# Connectors_OLD.net
KiCad netlist of a schematic drawn in Altium Designer
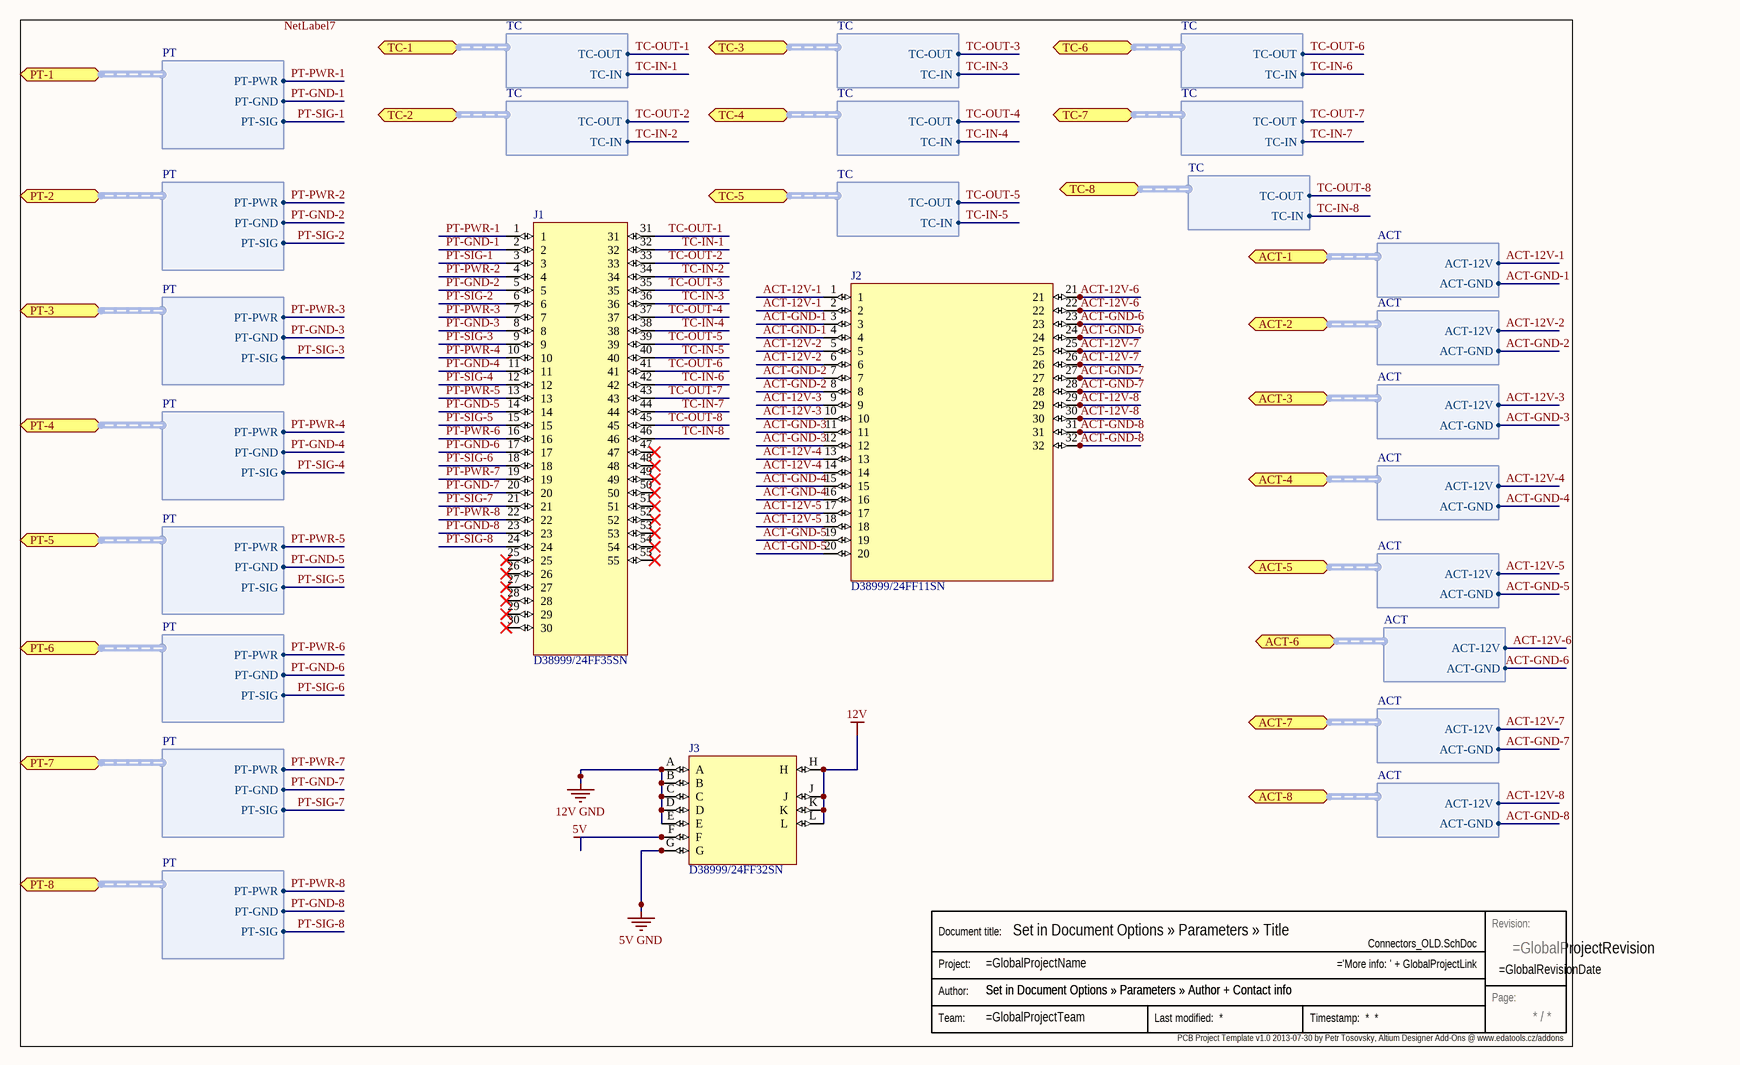
[diagram p0: Connectors_OLD.SchDoc]

(export (version "E")
  (design (tool "Eeschema 10.0.6"))
  (components
    (comp (ref "J1")
      (value "D38999/24FF35SN")
      (footprint "17-35")
      (description "D38999/24FE35SN")
      (libsource (lib "D38999 connectors") (part "D38999/24FF35SN"))
    )
    (comp (ref "J2")
      (value "D38999/24FF11SN")
      (footprint "19-32")
      (libsource (lib "D38999 connectors") (part "D38999/24FF11SN"))
    )
    (comp (ref "J3")
      (value "D38999/24FF32SN")
      (footprint "19-11")
      (libsource (lib "D38999 connectors") (part "D38999/24FF32SN"))
    )
    (comp (ref "Stamp") (value "Stamp") (libsource (lib "ShieldsLib") (part "Stamp")))
  )
  (nets
    (net (code "4") (name "/ACT-12V-1") (class "Default")
      (node (ref "J2") (pin "1") (pinfunction "1_1") (pintype "bidirectional"))
      (node (ref "J2") (pin "2") (pinfunction "2_2") (pintype "bidirectional"))
    )
    (net (code "5") (name "/ACT-12V-2") (class "Default")
      (node (ref "J2") (pin "5") (pinfunction "5_5") (pintype "bidirectional"))
      (node (ref "J2") (pin "6") (pinfunction "6_6") (pintype "bidirectional"))
    )
    (net (code "6") (name "/ACT-12V-3") (class "Default")
      (node (ref "J2") (pin "10") (pinfunction "10_10") (pintype "bidirectional"))
      (node (ref "J2") (pin "9") (pinfunction "9_9") (pintype "bidirectional"))
    )
    (net (code "7") (name "/ACT-12V-4") (class "Default")
      (node (ref "J2") (pin "13") (pinfunction "13_13") (pintype "bidirectional"))
      (node (ref "J2") (pin "14") (pinfunction "14_14") (pintype "bidirectional"))
    )
    (net (code "8") (name "/ACT-12V-5") (class "Default")
      (node (ref "J2") (pin "17") (pinfunction "17_17") (pintype "bidirectional"))
      (node (ref "J2") (pin "18") (pinfunction "18_18") (pintype "bidirectional"))
    )
    (net (code "9") (name "/ACT-12V-6") (class "Default")
      (node (ref "J2") (pin "21") (pinfunction "21_21") (pintype "bidirectional"))
      (node (ref "J2") (pin "22") (pinfunction "22_22") (pintype "bidirectional"))
    )
    (net (code "10") (name "/ACT-12V-7") (class "Default")
      (node (ref "J2") (pin "25") (pinfunction "25_25") (pintype "bidirectional"))
      (node (ref "J2") (pin "26") (pinfunction "26_26") (pintype "bidirectional"))
    )
    (net (code "11") (name "/ACT-12V-8") (class "Default")
      (node (ref "J2") (pin "29") (pinfunction "29_29") (pintype "bidirectional"))
      (node (ref "J2") (pin "30") (pinfunction "30_30") (pintype "bidirectional"))
    )
    (net (code "12") (name "/ACT-GND-1") (class "Default")
      (node (ref "J2") (pin "3") (pinfunction "3_3") (pintype "bidirectional"))
      (node (ref "J2") (pin "4") (pinfunction "4_4") (pintype "bidirectional"))
    )
    (net (code "13") (name "/ACT-GND-2") (class "Default")
      (node (ref "J2") (pin "7") (pinfunction "7_7") (pintype "bidirectional"))
      (node (ref "J2") (pin "8") (pinfunction "8_8") (pintype "bidirectional"))
    )
    (net (code "14") (name "/ACT-GND-3") (class "Default")
      (node (ref "J2") (pin "11") (pinfunction "11_11") (pintype "bidirectional"))
      (node (ref "J2") (pin "12") (pinfunction "12_12") (pintype "bidirectional"))
    )
    (net (code "15") (name "/ACT-GND-4") (class "Default")
      (node (ref "J2") (pin "15") (pinfunction "15_15") (pintype "bidirectional"))
      (node (ref "J2") (pin "16") (pinfunction "16_16") (pintype "bidirectional"))
    )
    (net (code "16") (name "/ACT-GND-5") (class "Default")
      (node (ref "J2") (pin "19") (pinfunction "19_19") (pintype "bidirectional"))
      (node (ref "J2") (pin "20") (pinfunction "20_20") (pintype "bidirectional"))
    )
    (net (code "17") (name "/ACT-GND-6") (class "Default")
      (node (ref "J2") (pin "23") (pinfunction "23_23") (pintype "bidirectional"))
      (node (ref "J2") (pin "24") (pinfunction "24_24") (pintype "bidirectional"))
    )
    (net (code "18") (name "/ACT-GND-7") (class "Default")
      (node (ref "J2") (pin "27") (pinfunction "27_27") (pintype "bidirectional"))
      (node (ref "J2") (pin "28") (pinfunction "28_28") (pintype "bidirectional"))
    )
    (net (code "19") (name "/ACT-GND-8") (class "Default")
      (node (ref "J2") (pin "31") (pinfunction "31_31") (pintype "bidirectional"))
      (node (ref "J2") (pin "32") (pinfunction "32_32") (pintype "bidirectional"))
    )
    (net (code "21") (name "/PT-GND-1") (class "Default")
      (node (ref "J1") (pin "2") (pinfunction "2_2") (pintype "bidirectional"))
    )
    (net (code "22") (name "/PT-GND-2") (class "Default")
      (node (ref "J1") (pin "5") (pinfunction "5_5") (pintype "bidirectional"))
    )
    (net (code "23") (name "/PT-GND-3") (class "Default")
      (node (ref "J1") (pin "8") (pinfunction "8_8") (pintype "bidirectional"))
    )
    (net (code "24") (name "/PT-GND-4") (class "Default")
      (node (ref "J1") (pin "11") (pinfunction "11_11") (pintype "bidirectional"))
    )
    (net (code "25") (name "/PT-GND-5") (class "Default")
      (node (ref "J1") (pin "14") (pinfunction "14_14") (pintype "bidirectional"))
    )
    (net (code "26") (name "/PT-GND-6") (class "Default")
      (node (ref "J1") (pin "17") (pinfunction "17_17") (pintype "bidirectional"))
    )
    (net (code "27") (name "/PT-GND-7") (class "Default")
      (node (ref "J1") (pin "20") (pinfunction "20_20") (pintype "bidirectional"))
    )
    (net (code "28") (name "/PT-GND-8") (class "Default")
      (node (ref "J1") (pin "23") (pinfunction "23_23") (pintype "bidirectional"))
    )
    (net (code "29") (name "/PT-PWR-1") (class "Default")
      (node (ref "J1") (pin "1") (pinfunction "1_1") (pintype "bidirectional"))
    )
    (net (code "30") (name "/PT-PWR-2") (class "Default")
      (node (ref "J1") (pin "4") (pinfunction "4_4") (pintype "bidirectional"))
    )
    (net (code "31") (name "/PT-PWR-3") (class "Default")
      (node (ref "J1") (pin "7") (pinfunction "7_7") (pintype "bidirectional"))
    )
    (net (code "32") (name "/PT-PWR-4") (class "Default")
      (node (ref "J1") (pin "10") (pinfunction "10_10") (pintype "bidirectional"))
    )
    (net (code "33") (name "/PT-PWR-5") (class "Default")
      (node (ref "J1") (pin "13") (pinfunction "13_13") (pintype "bidirectional"))
    )
    (net (code "34") (name "/PT-PWR-6") (class "Default")
      (node (ref "J1") (pin "16") (pinfunction "16_16") (pintype "bidirectional"))
    )
    (net (code "35") (name "/PT-PWR-7") (class "Default")
      (node (ref "J1") (pin "19") (pinfunction "19_19") (pintype "bidirectional"))
    )
    (net (code "36") (name "/PT-PWR-8") (class "Default")
      (node (ref "J1") (pin "22") (pinfunction "22_22") (pintype "bidirectional"))
    )
    (net (code "37") (name "/PT-SIG-1") (class "Default")
      (node (ref "J1") (pin "3") (pinfunction "3_3") (pintype "bidirectional"))
    )
    (net (code "38") (name "/PT-SIG-2") (class "Default")
      (node (ref "J1") (pin "6") (pinfunction "6_6") (pintype "bidirectional"))
    )
    (net (code "39") (name "/PT-SIG-3") (class "Default")
      (node (ref "J1") (pin "9") (pinfunction "9_9") (pintype "bidirectional"))
    )
    (net (code "40") (name "/PT-SIG-4") (class "Default")
      (node (ref "J1") (pin "12") (pinfunction "12_12") (pintype "bidirectional"))
    )
    (net (code "41") (name "/PT-SIG-5") (class "Default")
      (node (ref "J1") (pin "15") (pinfunction "15_15") (pintype "bidirectional"))
    )
    (net (code "42") (name "/PT-SIG-6") (class "Default")
      (node (ref "J1") (pin "18") (pinfunction "18_18") (pintype "bidirectional"))
    )
    (net (code "43") (name "/PT-SIG-7") (class "Default")
      (node (ref "J1") (pin "21") (pinfunction "21_21") (pintype "bidirectional"))
    )
    (net (code "44") (name "/PT-SIG-8") (class "Default")
      (node (ref "J1") (pin "24") (pinfunction "24_24") (pintype "bidirectional"))
    )
    (net (code "45") (name "/TC-IN-1") (class "Default")
      (node (ref "J1") (pin "32") (pinfunction "32_32") (pintype "bidirectional"))
    )
    (net (code "46") (name "/TC-IN-2") (class "Default")
      (node (ref "J1") (pin "34") (pinfunction "34_34") (pintype "bidirectional"))
    )
    (net (code "47") (name "/TC-IN-3") (class "Default")
      (node (ref "J1") (pin "36") (pinfunction "36_36") (pintype "bidirectional"))
    )
    (net (code "48") (name "/TC-IN-4") (class "Default")
      (node (ref "J1") (pin "38") (pinfunction "38_38") (pintype "bidirectional"))
    )
    (net (code "49") (name "/TC-IN-5") (class "Default")
      (node (ref "J1") (pin "40") (pinfunction "40_40") (pintype "bidirectional"))
    )
    (net (code "50") (name "/TC-IN-6") (class "Default")
      (node (ref "J1") (pin "42") (pinfunction "42_42") (pintype "bidirectional"))
    )
    (net (code "51") (name "/TC-IN-7") (class "Default")
      (node (ref "J1") (pin "44") (pinfunction "44_44") (pintype "bidirectional"))
    )
    (net (code "52") (name "/TC-IN-8") (class "Default")
      (node (ref "J1") (pin "46") (pinfunction "46_46") (pintype "bidirectional"))
    )
    (net (code "53") (name "/TC-OUT-1") (class "Default")
      (node (ref "J1") (pin "31") (pinfunction "31_31") (pintype "bidirectional"))
    )
    (net (code "54") (name "/TC-OUT-2") (class "Default")
      (node (ref "J1") (pin "33") (pinfunction "33_33") (pintype "bidirectional"))
    )
    (net (code "55") (name "/TC-OUT-3") (class "Default")
      (node (ref "J1") (pin "35") (pinfunction "35_35") (pintype "bidirectional"))
    )
    (net (code "56") (name "/TC-OUT-4") (class "Default")
      (node (ref "J1") (pin "37") (pinfunction "37_37") (pintype "bidirectional"))
    )
    (net (code "57") (name "/TC-OUT-5") (class "Default")
      (node (ref "J1") (pin "39") (pinfunction "39_39") (pintype "bidirectional"))
    )
    (net (code "58") (name "/TC-OUT-6") (class "Default")
      (node (ref "J1") (pin "41") (pinfunction "41_41") (pintype "bidirectional"))
    )
    (net (code "59") (name "/TC-OUT-7") (class "Default")
      (node (ref "J1") (pin "43") (pinfunction "43_43") (pintype "bidirectional"))
    )
    (net (code "60") (name "/TC-OUT-8") (class "Default")
      (node (ref "J1") (pin "45") (pinfunction "45_45") (pintype "bidirectional"))
    )
    (net (code "64") (name "5V") (class "Default")
      (node (ref "J3") (pin "F") (pinfunction "F_F") (pintype "bidirectional"))
    )
    (net (code "65") (name "5V GND") (class "Default")
      (node (ref "J3") (pin "G") (pinfunction "G_G") (pintype "bidirectional"))
    )
    (net (code "66") (name "12V") (class "Default")
      (node (ref "J3") (pin "H") (pinfunction "H_H") (pintype "bidirectional"))
      (node (ref "J3") (pin "J") (pinfunction "J_J") (pintype "bidirectional"))
      (node (ref "J3") (pin "K") (pinfunction "K_K") (pintype "bidirectional"))
      (node (ref "J3") (pin "L") (pinfunction "L_L") (pintype "bidirectional"))
    )
    (net (code "67") (name "12V GND") (class "Default")
      (node (ref "J3") (pin "A") (pinfunction "A_A") (pintype "bidirectional"))
      (node (ref "J3") (pin "B") (pinfunction "B_B") (pintype "bidirectional"))
      (node (ref "J3") (pin "C") (pinfunction "C_C") (pintype "bidirectional"))
      (node (ref "J3") (pin "D") (pinfunction "D_D") (pintype "bidirectional"))
      (node (ref "J3") (pin "E") (pinfunction "E_E") (pintype "bidirectional"))
    )
    (net (code "68") (name "unconnected-(J1-Pad25)") (class "Default")
      (node (ref "J1") (pin "25") (pinfunction "25_25") (pintype "bidirectional+no_connect"))
    )
    (net (code "69") (name "unconnected-(J1-Pad26)") (class "Default")
      (node (ref "J1") (pin "26") (pinfunction "26_26") (pintype "bidirectional+no_connect"))
    )
    (net (code "70") (name "unconnected-(J1-Pad27)") (class "Default")
      (node (ref "J1") (pin "27") (pinfunction "27_27") (pintype "bidirectional+no_connect"))
    )
    (net (code "71") (name "unconnected-(J1-Pad28)") (class "Default")
      (node (ref "J1") (pin "28") (pinfunction "28_28") (pintype "bidirectional+no_connect"))
    )
    (net (code "72") (name "unconnected-(J1-Pad29)") (class "Default")
      (node (ref "J1") (pin "29") (pinfunction "29_29") (pintype "bidirectional+no_connect"))
    )
    (net (code "73") (name "unconnected-(J1-Pad30)") (class "Default")
      (node (ref "J1") (pin "30") (pinfunction "30_30") (pintype "bidirectional+no_connect"))
    )
    (net (code "74") (name "unconnected-(J1-Pad47)") (class "Default")
      (node (ref "J1") (pin "47") (pinfunction "47_47") (pintype "bidirectional+no_connect"))
    )
    (net (code "75") (name "unconnected-(J1-Pad48)") (class "Default")
      (node (ref "J1") (pin "48") (pinfunction "48_48") (pintype "bidirectional+no_connect"))
    )
    (net (code "76") (name "unconnected-(J1-Pad49)") (class "Default")
      (node (ref "J1") (pin "49") (pinfunction "49_49") (pintype "bidirectional+no_connect"))
    )
    (net (code "77") (name "unconnected-(J1-Pad50)") (class "Default")
      (node (ref "J1") (pin "50") (pinfunction "50_50") (pintype "bidirectional+no_connect"))
    )
    (net (code "78") (name "unconnected-(J1-Pad51)") (class "Default")
      (node (ref "J1") (pin "51") (pinfunction "51_51") (pintype "bidirectional+no_connect"))
    )
    (net (code "79") (name "unconnected-(J1-Pad52)") (class "Default")
      (node (ref "J1") (pin "52") (pinfunction "52_52") (pintype "bidirectional+no_connect"))
    )
    (net (code "80") (name "unconnected-(J1-Pad53)") (class "Default")
      (node (ref "J1") (pin "53") (pinfunction "53_53") (pintype "bidirectional+no_connect"))
    )
    (net (code "81") (name "unconnected-(J1-Pad54)") (class "Default")
      (node (ref "J1") (pin "54") (pinfunction "54_54") (pintype "bidirectional+no_connect"))
    )
    (net (code "82") (name "unconnected-(J1-Pad55)") (class "Default")
      (node (ref "J1") (pin "55") (pinfunction "55_55") (pintype "bidirectional+no_connect"))
    )
  )
)
